# AJH_ss12144_v1_02.net
KiCad netlist of a schematic drawn in EAGLE
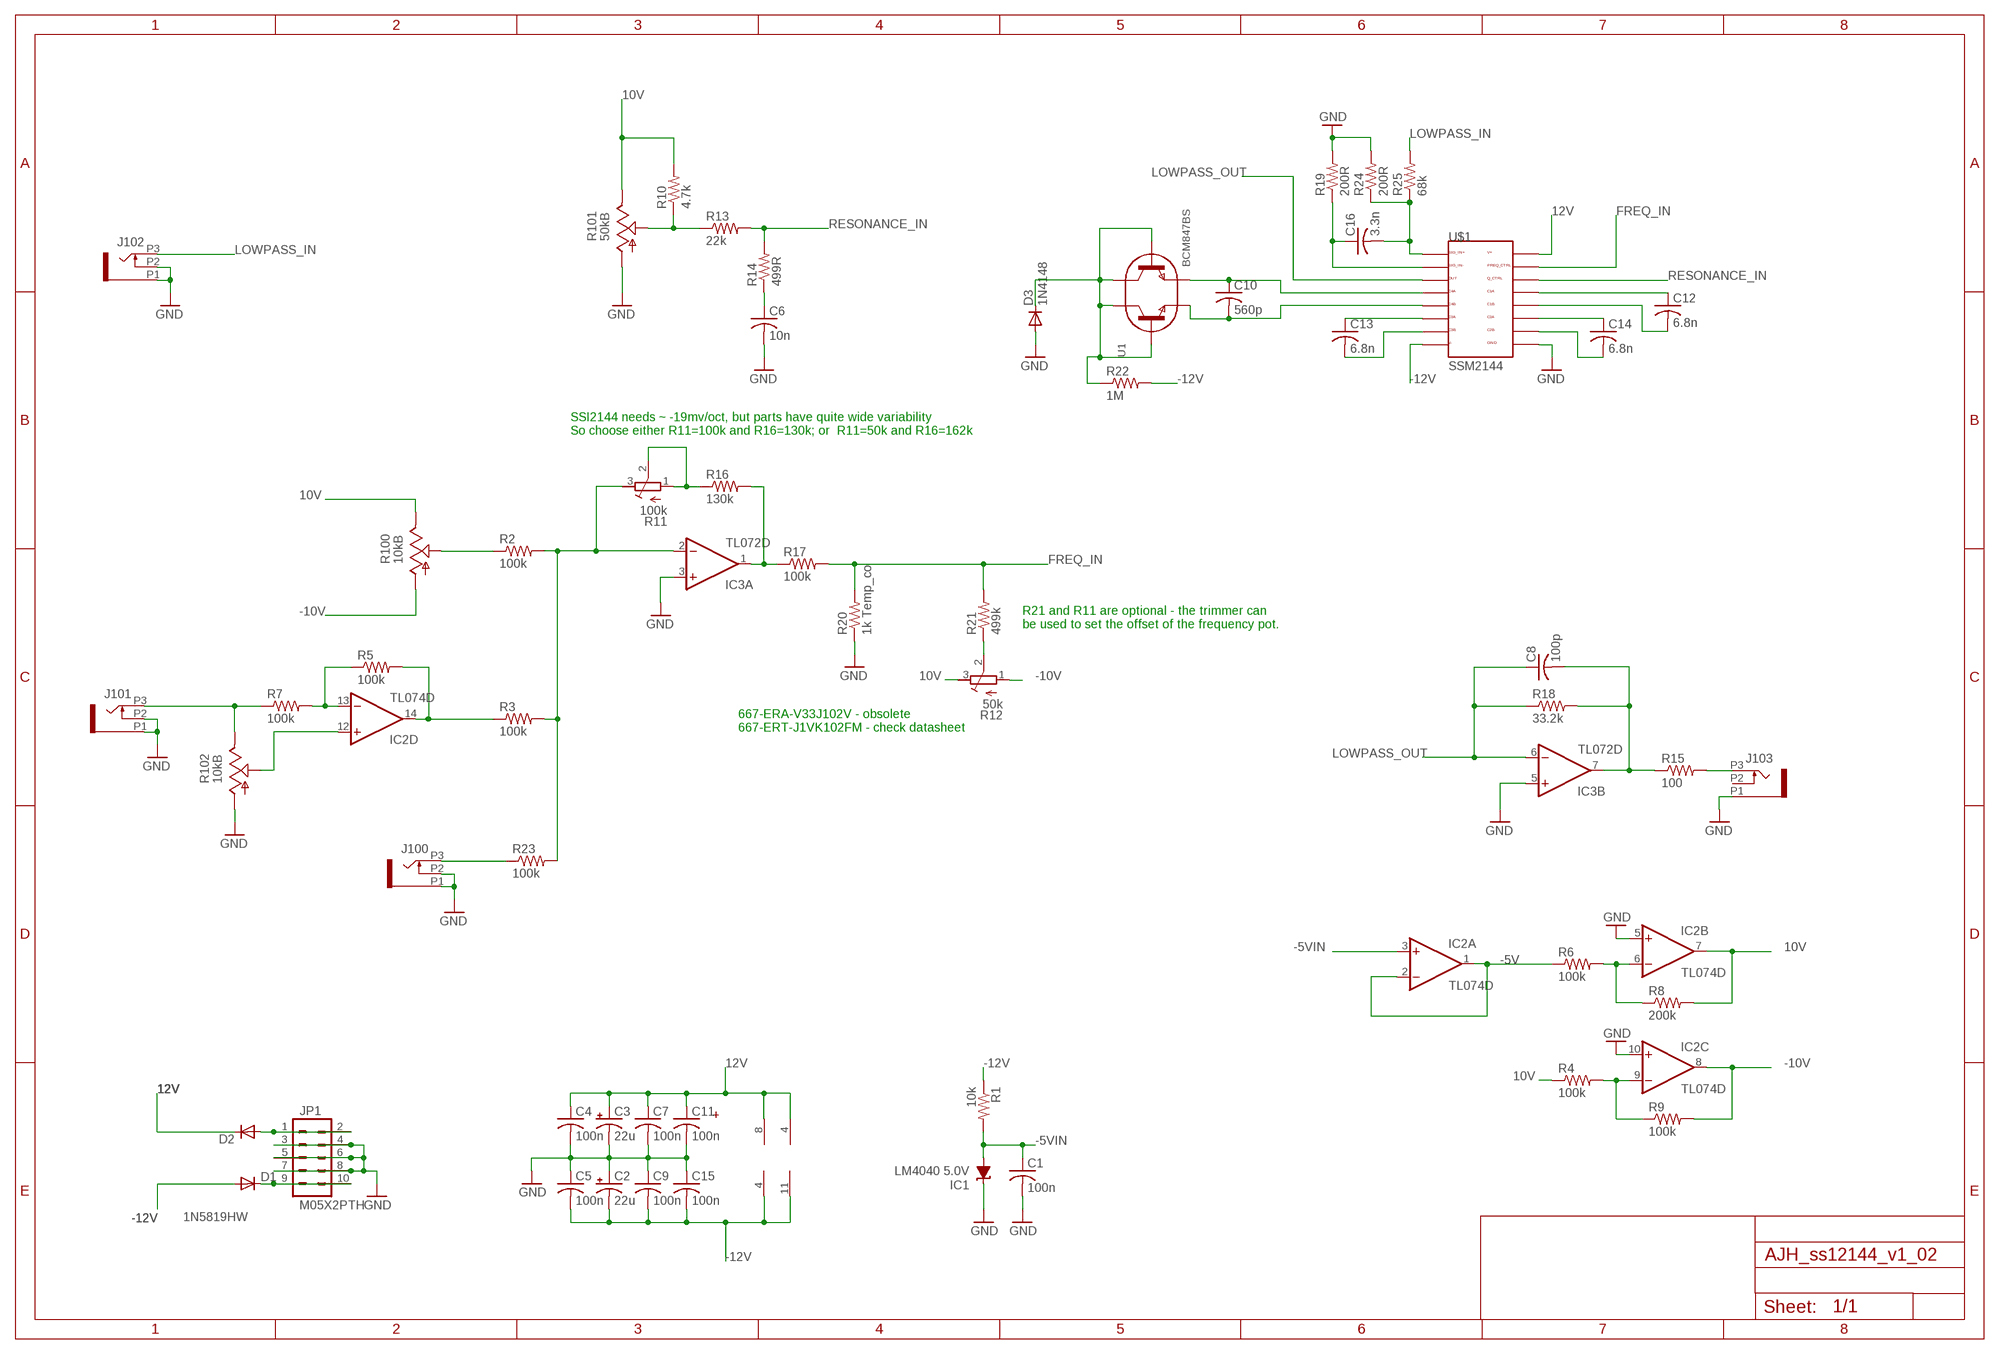
[diagram p0: schematic, sheet 1]

(export (version "E")
  (design (tool "Eeschema 10.0.6"))
  (components
    (comp (ref "C1")
      (value "100n")
      (footprint "eagle-import:C0603")
      (libsource (lib "eagle-import") (part "C-USC0603"))
    )
    (comp (ref "C2")
      (value "22u")
      (footprint "eagle-import:PANASONIC_B")
      (libsource (lib "eagle-import") (part "CPOL-USB"))
    )
    (comp (ref "C3")
      (value "22u")
      (footprint "eagle-import:PANASONIC_B")
      (libsource (lib "eagle-import") (part "CPOL-USB"))
    )
    (comp (ref "C4")
      (value "100n")
      (footprint "eagle-import:C0603")
      (libsource (lib "eagle-import") (part "C-USC0603"))
    )
    (comp (ref "C5")
      (value "100n")
      (footprint "eagle-import:C0603")
      (libsource (lib "eagle-import") (part "C-USC0603"))
    )
    (comp (ref "C6")
      (value "10n")
      (footprint "eagle-import:C0603")
      (libsource (lib "eagle-import") (part "C-USC0603"))
    )
    (comp (ref "C7")
      (value "100n")
      (footprint "eagle-import:C0603")
      (libsource (lib "eagle-import") (part "C-USC0603"))
    )
    (comp (ref "C8")
      (value "100p")
      (footprint "eagle-import:C0603")
      (libsource (lib "eagle-import") (part "C-USC0603"))
    )
    (comp (ref "C9")
      (value "100n")
      (footprint "eagle-import:C0603")
      (libsource (lib "eagle-import") (part "C-USC0603"))
    )
    (comp (ref "C10")
      (value "560p")
      (footprint "eagle-import:C0603")
      (libsource (lib "eagle-import") (part "C-USC0603"))
    )
    (comp (ref "C11")
      (value "100n")
      (footprint "eagle-import:C0603")
      (libsource (lib "eagle-import") (part "C-USC0603"))
    )
    (comp (ref "C12")
      (value "6.8n")
      (footprint "eagle-import:C0603")
      (libsource (lib "eagle-import") (part "C-USC0603"))
    )
    (comp (ref "C13")
      (value "6.8n")
      (footprint "eagle-import:C0603")
      (libsource (lib "eagle-import") (part "C-USC0603"))
    )
    (comp (ref "C14")
      (value "6.8n")
      (footprint "eagle-import:C0603")
      (libsource (lib "eagle-import") (part "C-USC0603"))
    )
    (comp (ref "C15")
      (value "100n")
      (footprint "eagle-import:C0603")
      (libsource (lib "eagle-import") (part "C-USC0603"))
    )
    (comp (ref "C16")
      (value "3.3n")
      (footprint "eagle-import:C0603")
      (libsource (lib "eagle-import") (part "C-USC0603"))
    )
    (comp (ref "D1")
      (value "1N5819HW")
      (footprint "eagle-import:SOD123")
      (libsource (lib "eagle-import") (part "DIODE-SOD123"))
    )
    (comp (ref "D2")
      (value "1N5819HW")
      (footprint "eagle-import:SOD123")
      (libsource (lib "eagle-import") (part "DIODE-SOD123"))
    )
    (comp (ref "D3")
      (value "1N4148")
      (footprint "eagle-import:SOD523")
      (libsource (lib "eagle-import") (part "DIODE-SOD523"))
    )
    (comp (ref "IC1")
      (value "LM4040 5.0V")
      (footprint "eagle-import:DBZ_R-PDSO-G3")
      (libsource (lib "eagle-import") (part "LM4041DBZC12"))
    )
    (comp (ref "IC2")
      (value "TL074D")
      (footprint "eagle-import:SO14")
      (libsource (lib "eagle-import") (part "TL074D"))
    )
    (comp (ref "IC3")
      (value "TL072D")
      (footprint "eagle-import:SO08")
      (libsource (lib "eagle-import") (part "TL072D"))
    )
    (comp (ref "J100")
      (value "PJ301_THONKICONN6")
      (footprint "eagle-import:WQP_PJ_301M6")
      (libsource (lib "eagle-import") (part "PJ301_THONKICONN6"))
    )
    (comp (ref "J101")
      (value "PJ301_THONKICONN6")
      (footprint "eagle-import:WQP_PJ_301M6")
      (libsource (lib "eagle-import") (part "PJ301_THONKICONN6"))
    )
    (comp (ref "J102")
      (value "PJ301_THONKICONN6")
      (footprint "eagle-import:WQP_PJ_301M6")
      (libsource (lib "eagle-import") (part "PJ301_THONKICONN6"))
    )
    (comp (ref "J103")
      (value "PJ301_THONKICONN6")
      (footprint "eagle-import:WQP_PJ_301M6")
      (libsource (lib "eagle-import") (part "PJ301_THONKICONN6"))
    )
    (comp (ref "JP1")
      (value "M05X2PTH")
      (footprint "eagle-import:AVR_ICSP")
      (libsource (lib "eagle-import") (part "M05X2PTH"))
    )
    (comp (ref "R1")
      (value "10k")
      (footprint "eagle-import:R0603")
      (libsource (lib "eagle-import") (part "R-US_R0603"))
    )
    (comp (ref "R2")
      (value "100k")
      (footprint "eagle-import:R0603")
      (libsource (lib "eagle-import") (part "R-US_R0603"))
    )
    (comp (ref "R3")
      (value "100k")
      (footprint "eagle-import:R0603")
      (libsource (lib "eagle-import") (part "R-US_R0603"))
    )
    (comp (ref "R4")
      (value "100k")
      (footprint "eagle-import:R0603")
      (libsource (lib "eagle-import") (part "R-US_R0603"))
    )
    (comp (ref "R5")
      (value "100k")
      (footprint "eagle-import:R0603")
      (libsource (lib "eagle-import") (part "R-US_R0603"))
    )
    (comp (ref "R6")
      (value "100k")
      (footprint "eagle-import:R0603")
      (libsource (lib "eagle-import") (part "R-US_R0603"))
    )
    (comp (ref "R7")
      (value "100k")
      (footprint "eagle-import:R0603")
      (libsource (lib "eagle-import") (part "R-US_R0603"))
    )
    (comp (ref "R8")
      (value "200k")
      (footprint "eagle-import:R0603")
      (libsource (lib "eagle-import") (part "R-US_R0603"))
    )
    (comp (ref "R9")
      (value "100k")
      (footprint "eagle-import:R0603")
      (libsource (lib "eagle-import") (part "R-US_R0603"))
    )
    (comp (ref "R10")
      (value "4.7k")
      (footprint "eagle-import:R0603")
      (libsource (lib "eagle-import") (part "R-US_R0603"))
    )
    (comp (ref "R11")
      (value "100k")
      (footprint "eagle-import:RTRIM3296X")
      (libsource (lib "eagle-import") (part "R-TRIMM3296X"))
    )
    (comp (ref "R12")
      (value "50k")
      (footprint "eagle-import:RTRIM3296X")
      (libsource (lib "eagle-import") (part "R-TRIMM3296X"))
    )
    (comp (ref "R13")
      (value "22k")
      (footprint "eagle-import:R0603")
      (libsource (lib "eagle-import") (part "R-US_R0603"))
    )
    (comp (ref "R14")
      (value "499R")
      (footprint "eagle-import:R0603")
      (libsource (lib "eagle-import") (part "R-US_R0603"))
    )
    (comp (ref "R15")
      (value "100")
      (footprint "eagle-import:R0603")
      (libsource (lib "eagle-import") (part "R-US_R0603"))
    )
    (comp (ref "R16")
      (value "130k")
      (footprint "eagle-import:R0603")
      (libsource (lib "eagle-import") (part "R-US_R0603"))
    )
    (comp (ref "R17")
      (value "100k")
      (footprint "eagle-import:R0603")
      (libsource (lib "eagle-import") (part "R-US_R0603"))
    )
    (comp (ref "R18")
      (value "33.2k")
      (footprint "eagle-import:R0603")
      (libsource (lib "eagle-import") (part "R-US_R0603"))
    )
    (comp (ref "R19")
      (value "200R")
      (footprint "eagle-import:R0603")
      (libsource (lib "eagle-import") (part "R-US_R0603"))
    )
    (comp (ref "R20")
      (value "1k Temp_co")
      (footprint "eagle-import:R0603")
      (libsource (lib "eagle-import") (part "R-US_R0603"))
    )
    (comp (ref "R21")
      (value "499k")
      (footprint "eagle-import:R0603")
      (libsource (lib "eagle-import") (part "R-US_R0603"))
    )
    (comp (ref "R22")
      (value "1M")
      (footprint "eagle-import:R0603")
      (libsource (lib "eagle-import") (part "R-US_R0603"))
    )
    (comp (ref "R23")
      (value "100k")
      (footprint "eagle-import:R0603")
      (libsource (lib "eagle-import") (part "R-US_R0603"))
    )
    (comp (ref "R24")
      (value "200R")
      (footprint "eagle-import:R0603")
      (libsource (lib "eagle-import") (part "R-US_R0603"))
    )
    (comp (ref "R25")
      (value "68k")
      (footprint "eagle-import:R0603")
      (libsource (lib "eagle-import") (part "R-US_R0603"))
    )
    (comp (ref "R100")
      (value "10kB")
      (footprint "eagle-import:ALPS_POT_VERTICAL")
      (libsource (lib "eagle-import") (part "POT_USVERTICAL"))
    )
    (comp (ref "R101")
      (value "50kB")
      (footprint "eagle-import:ALPS_POT_VERTICAL")
      (libsource (lib "eagle-import") (part "POT_USVERTICAL"))
    )
    (comp (ref "R102")
      (value "10kB")
      (footprint "eagle-import:ALPS_POT_VERTICAL")
      (libsource (lib "eagle-import") (part "POT_USVERTICAL"))
    )
    (comp (ref "U$1")
      (value "SSM2144")
      (footprint "eagle-import:SSOP16")
      (libsource (lib "eagle-import") (part "SSM2144"))
    )
    (comp (ref "U1")
      (value "BCM847BS")
      (footprint "eagle-import:SOT363")
      (libsource (lib "eagle-import") (part "BCM847BS"))
    )
  )
  (nets
    (net (code "1") (name "/-5V") (class "Default")
      (node (ref "IC2") (pin "1") (pinfunction "OUT_1") (pintype "output"))
      (node (ref "IC2") (pin "2") (pinfunction "-IN_2") (pintype "input"))
      (node (ref "R6") (pin "1") (pinfunction "1_1") (pintype "passive"))
    )
    (net (code "2") (name "/-5VIN") (class "Default")
      (node (ref "C1") (pin "1") (pinfunction "1_1") (pintype "passive"))
      (node (ref "IC1") (pin "2") (pinfunction "A_2") (pintype "passive"))
      (node (ref "IC2") (pin "3") (pinfunction "+IN_3") (pintype "input"))
      (node (ref "R1") (pin "2") (pinfunction "2_2") (pintype "passive"))
    )
    (net (code "3") (name "/-10V") (class "Default")
      (node (ref "IC2") (pin "8") (pinfunction "OUT_8") (pintype "output"))
      (node (ref "R100") (pin "P$3") (pinfunction "A_P$3") (pintype "passive"))
      (node (ref "R12") (pin "1") (pinfunction "E_1") (pintype "passive"))
      (node (ref "R9") (pin "2") (pinfunction "2_2") (pintype "passive"))
    )
    (net (code "4") (name "/-12V") (class "Default")
      (node (ref "C15") (pin "2") (pinfunction "2_2") (pintype "passive"))
      (node (ref "C2") (pin "-") (pinfunction "-_-") (pintype "passive"))
      (node (ref "C5") (pin "2") (pinfunction "2_2") (pintype "passive"))
      (node (ref "C9") (pin "2") (pinfunction "2_2") (pintype "passive"))
      (node (ref "D1") (pin "A") (pinfunction "A_A") (pintype "passive"))
      (node (ref "IC2") (pin "11") (pinfunction "V-_11") (pintype "power_in"))
      (node (ref "IC3") (pin "4") (pinfunction "V-_4") (pintype "power_in"))
      (node (ref "R1") (pin "1") (pinfunction "1_1") (pintype "passive"))
      (node (ref "R22") (pin "2") (pinfunction "2_2") (pintype "passive"))
      (node (ref "U$1") (pin "8") (pinfunction "V-_8") (pintype "bidirectional"))
    )
    (net (code "5") (name "/10V") (class "Default")
      (node (ref "IC2") (pin "7") (pinfunction "OUT_7") (pintype "output"))
      (node (ref "R10") (pin "2") (pinfunction "2_2") (pintype "passive"))
      (node (ref "R100") (pin "P$1") (pinfunction "E_P$1") (pintype "passive"))
      (node (ref "R101") (pin "P$1") (pinfunction "E_P$1") (pintype "passive"))
      (node (ref "R12") (pin "3") (pinfunction "A_3") (pintype "passive"))
      (node (ref "R4") (pin "1") (pinfunction "1_1") (pintype "passive"))
      (node (ref "R8") (pin "2") (pinfunction "2_2") (pintype "passive"))
    )
    (net (code "6") (name "/12V") (class "Default")
      (node (ref "C11") (pin "1") (pinfunction "1_1") (pintype "passive"))
      (node (ref "C3") (pin "+") (pinfunction "+_+") (pintype "passive"))
      (node (ref "C4") (pin "1") (pinfunction "1_1") (pintype "passive"))
      (node (ref "C7") (pin "1") (pinfunction "1_1") (pintype "passive"))
      (node (ref "D2") (pin "C") (pinfunction "C_C") (pintype "passive"))
      (node (ref "IC2") (pin "4") (pinfunction "V+_4") (pintype "power_in"))
      (node (ref "IC3") (pin "8") (pinfunction "V+_8") (pintype "power_in"))
      (node (ref "U$1") (pin "16") (pinfunction "V+_16") (pintype "bidirectional"))
    )
    (net (code "7") (name "/FREQ_IN") (class "Default")
      (node (ref "R17") (pin "2") (pinfunction "2_2") (pintype "passive"))
      (node (ref "R20") (pin "2") (pinfunction "2_2") (pintype "passive"))
      (node (ref "R21") (pin "2") (pinfunction "2_2") (pintype "passive"))
      (node (ref "U$1") (pin "15") (pinfunction "FREQ_CTRL_15") (pintype "bidirectional"))
    )
    (net (code "8") (name "/LOWPASS_IN") (class "Default")
      (node (ref "J102") (pin "P3") (pinfunction "3_P3") (pintype "passive"))
      (node (ref "R25") (pin "2") (pinfunction "2_2") (pintype "passive"))
    )
    (net (code "9") (name "/LOWPASS_OUT") (class "Default")
      (node (ref "C8") (pin "1") (pinfunction "1_1") (pintype "passive"))
      (node (ref "IC3") (pin "6") (pinfunction "-IN_6") (pintype "input"))
      (node (ref "R18") (pin "1") (pinfunction "1_1") (pintype "passive"))
      (node (ref "U$1") (pin "3") (pinfunction "OUT_3") (pintype "bidirectional"))
    )
    (net (code "10") (name "/RESONANCE_IN") (class "Default")
      (node (ref "R13") (pin "2") (pinfunction "2_2") (pintype "passive"))
      (node (ref "R14") (pin "2") (pinfunction "2_2") (pintype "passive"))
      (node (ref "U$1") (pin "14") (pinfunction "Q_CTRL_14") (pintype "bidirectional"))
    )
    (net (code "11") (name "GND") (class "Default")
      (node (ref "C1") (pin "2") (pinfunction "2_2") (pintype "passive"))
      (node (ref "C11") (pin "2") (pinfunction "2_2") (pintype "passive"))
      (node (ref "C15") (pin "1") (pinfunction "1_1") (pintype "passive"))
      (node (ref "C2") (pin "+") (pinfunction "+_+") (pintype "passive"))
      (node (ref "C3") (pin "-") (pinfunction "-_-") (pintype "passive"))
      (node (ref "C4") (pin "2") (pinfunction "2_2") (pintype "passive"))
      (node (ref "C5") (pin "1") (pinfunction "1_1") (pintype "passive"))
      (node (ref "C6") (pin "2") (pinfunction "2_2") (pintype "passive"))
      (node (ref "C7") (pin "2") (pinfunction "2_2") (pintype "passive"))
      (node (ref "C9") (pin "1") (pinfunction "1_1") (pintype "passive"))
      (node (ref "D3") (pin "A") (pinfunction "A_A") (pintype "passive"))
      (node (ref "IC1") (pin "1") (pinfunction "C_1") (pintype "passive"))
      (node (ref "IC2") (pin "10") (pinfunction "+IN_10") (pintype "input"))
      (node (ref "IC2") (pin "5") (pinfunction "+IN_5") (pintype "input"))
      (node (ref "IC3") (pin "3") (pinfunction "+IN_3") (pintype "input"))
      (node (ref "IC3") (pin "5") (pinfunction "+IN_5") (pintype "input"))
      (node (ref "J100") (pin "P1") (pinfunction "1_P1") (pintype "passive"))
      (node (ref "J100") (pin "P2") (pinfunction "2_P2") (pintype "passive"))
      (node (ref "J101") (pin "P1") (pinfunction "1_P1") (pintype "passive"))
      (node (ref "J101") (pin "P2") (pinfunction "2_P2") (pintype "passive"))
      (node (ref "J102") (pin "P1") (pinfunction "1_P1") (pintype "passive"))
      (node (ref "J102") (pin "P2") (pinfunction "2_P2") (pintype "passive"))
      (node (ref "J103") (pin "P1") (pinfunction "1_P1") (pintype "passive"))
      (node (ref "JP1") (pin "3") (pinfunction "3_3") (pintype "passive"))
      (node (ref "JP1") (pin "4") (pinfunction "4_4") (pintype "passive"))
      (node (ref "JP1") (pin "5") (pinfunction "5_5") (pintype "passive"))
      (node (ref "JP1") (pin "6") (pinfunction "6_6") (pintype "passive"))
      (node (ref "JP1") (pin "7") (pinfunction "7_7") (pintype "passive"))
      (node (ref "JP1") (pin "8") (pinfunction "8_8") (pintype "passive"))
      (node (ref "R101") (pin "P$3") (pinfunction "A_P$3") (pintype "passive"))
      (node (ref "R102") (pin "P$3") (pinfunction "A_P$3") (pintype "passive"))
      (node (ref "R19") (pin "2") (pinfunction "2_2") (pintype "passive"))
      (node (ref "R20") (pin "1") (pinfunction "1_1") (pintype "passive"))
      (node (ref "R24") (pin "2") (pinfunction "2_2") (pintype "passive"))
      (node (ref "U$1") (pin "9") (pinfunction "GND_9") (pintype "bidirectional"))
    )
    (net (code "12") (name "Net-(C6-Pad1)") (class "Default")
      (node (ref "C6") (pin "1") (pinfunction "1_1") (pintype "passive"))
      (node (ref "R14") (pin "1") (pinfunction "1_1") (pintype "passive"))
    )
    (net (code "13") (name "Net-(D1-PadC)") (class "Default")
      (node (ref "D1") (pin "C") (pinfunction "C_C") (pintype "passive"))
      (node (ref "JP1") (pin "10") (pinfunction "10_10") (pintype "passive"))
      (node (ref "JP1") (pin "9") (pinfunction "9_9") (pintype "passive"))
    )
    (net (code "14") (name "Net-(D2-PadA)") (class "Default")
      (node (ref "D2") (pin "A") (pinfunction "A_A") (pintype "passive"))
      (node (ref "JP1") (pin "1") (pinfunction "1_1") (pintype "passive"))
      (node (ref "JP1") (pin "2") (pinfunction "2_2") (pintype "passive"))
    )
    (net (code "15") (name "Net-(IC2B--IN)") (class "Default")
      (node (ref "IC2") (pin "6") (pinfunction "-IN_6") (pintype "input"))
      (node (ref "R6") (pin "2") (pinfunction "2_2") (pintype "passive"))
      (node (ref "R8") (pin "1") (pinfunction "1_1") (pintype "passive"))
    )
    (net (code "16") (name "Net-(IC2C--IN)") (class "Default")
      (node (ref "IC2") (pin "9") (pinfunction "-IN_9") (pintype "input"))
      (node (ref "R4") (pin "2") (pinfunction "2_2") (pintype "passive"))
      (node (ref "R9") (pin "1") (pinfunction "1_1") (pintype "passive"))
    )
    (net (code "17") (name "Net-(IC2D-+IN)") (class "Default")
      (node (ref "IC2") (pin "12") (pinfunction "+IN_12") (pintype "input"))
      (node (ref "R102") (pin "P$2") (pinfunction "S_P$2") (pintype "passive"))
    )
    (net (code "18") (name "Net-(IC2D--IN)") (class "Default")
      (node (ref "IC2") (pin "13") (pinfunction "-IN_13") (pintype "input"))
      (node (ref "R5") (pin "1") (pinfunction "1_1") (pintype "passive"))
      (node (ref "R7") (pin "2") (pinfunction "2_2") (pintype "passive"))
    )
    (net (code "19") (name "Net-(IC2D-OUT)") (class "Default")
      (node (ref "IC2") (pin "14") (pinfunction "OUT_14") (pintype "output"))
      (node (ref "R3") (pin "1") (pinfunction "1_1") (pintype "passive"))
      (node (ref "R5") (pin "2") (pinfunction "2_2") (pintype "passive"))
    )
    (net (code "20") (name "Net-(IC3A--IN)") (class "Default")
      (node (ref "IC3") (pin "2") (pinfunction "-IN_2") (pintype "input"))
      (node (ref "R11") (pin "3") (pinfunction "A_3") (pintype "passive"))
      (node (ref "R2") (pin "2") (pinfunction "2_2") (pintype "passive"))
      (node (ref "R23") (pin "2") (pinfunction "2_2") (pintype "passive"))
      (node (ref "R3") (pin "2") (pinfunction "2_2") (pintype "passive"))
    )
    (net (code "21") (name "Net-(IC3A-OUT)") (class "Default")
      (node (ref "IC3") (pin "1") (pinfunction "OUT_1") (pintype "output"))
      (node (ref "R16") (pin "2") (pinfunction "2_2") (pintype "passive"))
      (node (ref "R17") (pin "1") (pinfunction "1_1") (pintype "passive"))
    )
    (net (code "22") (name "Net-(IC3B-OUT)") (class "Default")
      (node (ref "C8") (pin "2") (pinfunction "2_2") (pintype "passive"))
      (node (ref "IC3") (pin "7") (pinfunction "OUT_7") (pintype "output"))
      (node (ref "R15") (pin "1") (pinfunction "1_1") (pintype "passive"))
      (node (ref "R18") (pin "2") (pinfunction "2_2") (pintype "passive"))
    )
    (net (code "23") (name "Net-(J100-3)") (class "Default")
      (node (ref "J100") (pin "P3") (pinfunction "3_P3") (pintype "passive"))
      (node (ref "R23") (pin "1") (pinfunction "1_1") (pintype "passive"))
    )
    (net (code "24") (name "Net-(J101-3)") (class "Default")
      (node (ref "J101") (pin "P3") (pinfunction "3_P3") (pintype "passive"))
      (node (ref "R102") (pin "P$1") (pinfunction "E_P$1") (pintype "passive"))
      (node (ref "R7") (pin "1") (pinfunction "1_1") (pintype "passive"))
    )
    (net (code "25") (name "Net-(J103-3)") (class "Default")
      (node (ref "J103") (pin "P3") (pinfunction "3_P3") (pintype "passive"))
      (node (ref "R15") (pin "2") (pinfunction "2_2") (pintype "passive"))
    )
    (net (code "26") (name "Net-(R11-E)") (class "Default")
      (node (ref "R11") (pin "1") (pinfunction "E_1") (pintype "passive"))
      (node (ref "R11") (pin "2") (pinfunction "S_2") (pintype "passive"))
      (node (ref "R16") (pin "1") (pinfunction "1_1") (pintype "passive"))
    )
    (net (code "27") (name "Net-(R12-S)") (class "Default")
      (node (ref "R12") (pin "2") (pinfunction "S_2") (pintype "passive"))
      (node (ref "R21") (pin "1") (pinfunction "1_1") (pintype "passive"))
    )
    (net (code "28") (name "Net-(R100-S)") (class "Default")
      (node (ref "R100") (pin "P$2") (pinfunction "S_P$2") (pintype "passive"))
      (node (ref "R2") (pin "1") (pinfunction "1_1") (pintype "passive"))
    )
    (net (code "29") (name "Net-(R101-S)") (class "Default")
      (node (ref "R10") (pin "1") (pinfunction "1_1") (pintype "passive"))
      (node (ref "R101") (pin "P$2") (pinfunction "S_P$2") (pintype "passive"))
      (node (ref "R13") (pin "1") (pinfunction "1_1") (pintype "passive"))
    )
    (net (code "30") (name "Net-(U$1-C1A)") (class "Default")
      (node (ref "C12") (pin "1") (pinfunction "1_1") (pintype "passive"))
      (node (ref "U$1") (pin "13") (pinfunction "C1A_13") (pintype "bidirectional"))
    )
    (net (code "31") (name "Net-(U$1-C1B)") (class "Default")
      (node (ref "C12") (pin "2") (pinfunction "2_2") (pintype "passive"))
      (node (ref "U$1") (pin "12") (pinfunction "C1B_12") (pintype "bidirectional"))
    )
    (net (code "32") (name "Net-(U$1-C2A)") (class "Default")
      (node (ref "C14") (pin "1") (pinfunction "1_1") (pintype "passive"))
      (node (ref "U$1") (pin "11") (pinfunction "C2A_11") (pintype "bidirectional"))
    )
    (net (code "33") (name "Net-(U$1-C2B)") (class "Default")
      (node (ref "C14") (pin "2") (pinfunction "2_2") (pintype "passive"))
      (node (ref "U$1") (pin "10") (pinfunction "C2B_10") (pintype "bidirectional"))
    )
    (net (code "34") (name "Net-(U$1-C3A)") (class "Default")
      (node (ref "C13") (pin "1") (pinfunction "1_1") (pintype "passive"))
      (node (ref "U$1") (pin "6") (pinfunction "C3A_6") (pintype "bidirectional"))
    )
    (net (code "35") (name "Net-(U$1-C3B)") (class "Default")
      (node (ref "C13") (pin "2") (pinfunction "2_2") (pintype "passive"))
      (node (ref "U$1") (pin "7") (pinfunction "C3B_7") (pintype "bidirectional"))
    )
    (net (code "36") (name "Net-(U$1-C4A)") (class "Default")
      (node (ref "C10") (pin "1") (pinfunction "1_1") (pintype "passive"))
      (node (ref "U$1") (pin "4") (pinfunction "C4A_4") (pintype "bidirectional"))
      (node (ref "U1") (pin "4") (pinfunction "E2_4") (pintype "passive"))
    )
    (net (code "37") (name "Net-(U$1-C4B)") (class "Default")
      (node (ref "C10") (pin "2") (pinfunction "2_2") (pintype "passive"))
      (node (ref "U$1") (pin "5") (pinfunction "C4B_5") (pintype "bidirectional"))
      (node (ref "U1") (pin "1") (pinfunction "E1_1") (pintype "passive"))
    )
    (net (code "38") (name "Net-(U$1-SIG_IN+)") (class "Default")
      (node (ref "C16") (pin "2") (pinfunction "2_2") (pintype "passive"))
      (node (ref "R24") (pin "1") (pinfunction "1_1") (pintype "passive"))
      (node (ref "R25") (pin "1") (pinfunction "1_1") (pintype "passive"))
      (node (ref "U$1") (pin "1") (pinfunction "SIG_IN+_1") (pintype "bidirectional"))
    )
    (net (code "39") (name "Net-(U$1-SIG_IN-)") (class "Default")
      (node (ref "C16") (pin "1") (pinfunction "1_1") (pintype "passive"))
      (node (ref "R19") (pin "1") (pinfunction "1_1") (pintype "passive"))
      (node (ref "U$1") (pin "2") (pinfunction "SIG_IN-_2") (pintype "bidirectional"))
    )
    (net (code "40") (name "Net-(U1-B1)") (class "Default")
      (node (ref "D3") (pin "C") (pinfunction "C_C") (pintype "passive"))
      (node (ref "R22") (pin "1") (pinfunction "1_1") (pintype "passive"))
      (node (ref "U1") (pin "2") (pinfunction "B1_2") (pintype "passive"))
      (node (ref "U1") (pin "3") (pinfunction "C2_3") (pintype "passive"))
      (node (ref "U1") (pin "5") (pinfunction "B2_5") (pintype "passive"))
      (node (ref "U1") (pin "6") (pinfunction "C1_6") (pintype "passive"))
    )
    (net (code "41") (name "unconnected-(J103-2-PadP2)") (class "Default")
      (node (ref "J103") (pin "P2") (pinfunction "2_P2") (pintype "passive"))
    )
  )
)
